# Ollie_DriverMotors.net
KiCad netlist of a schematic drawn in Altium Designer
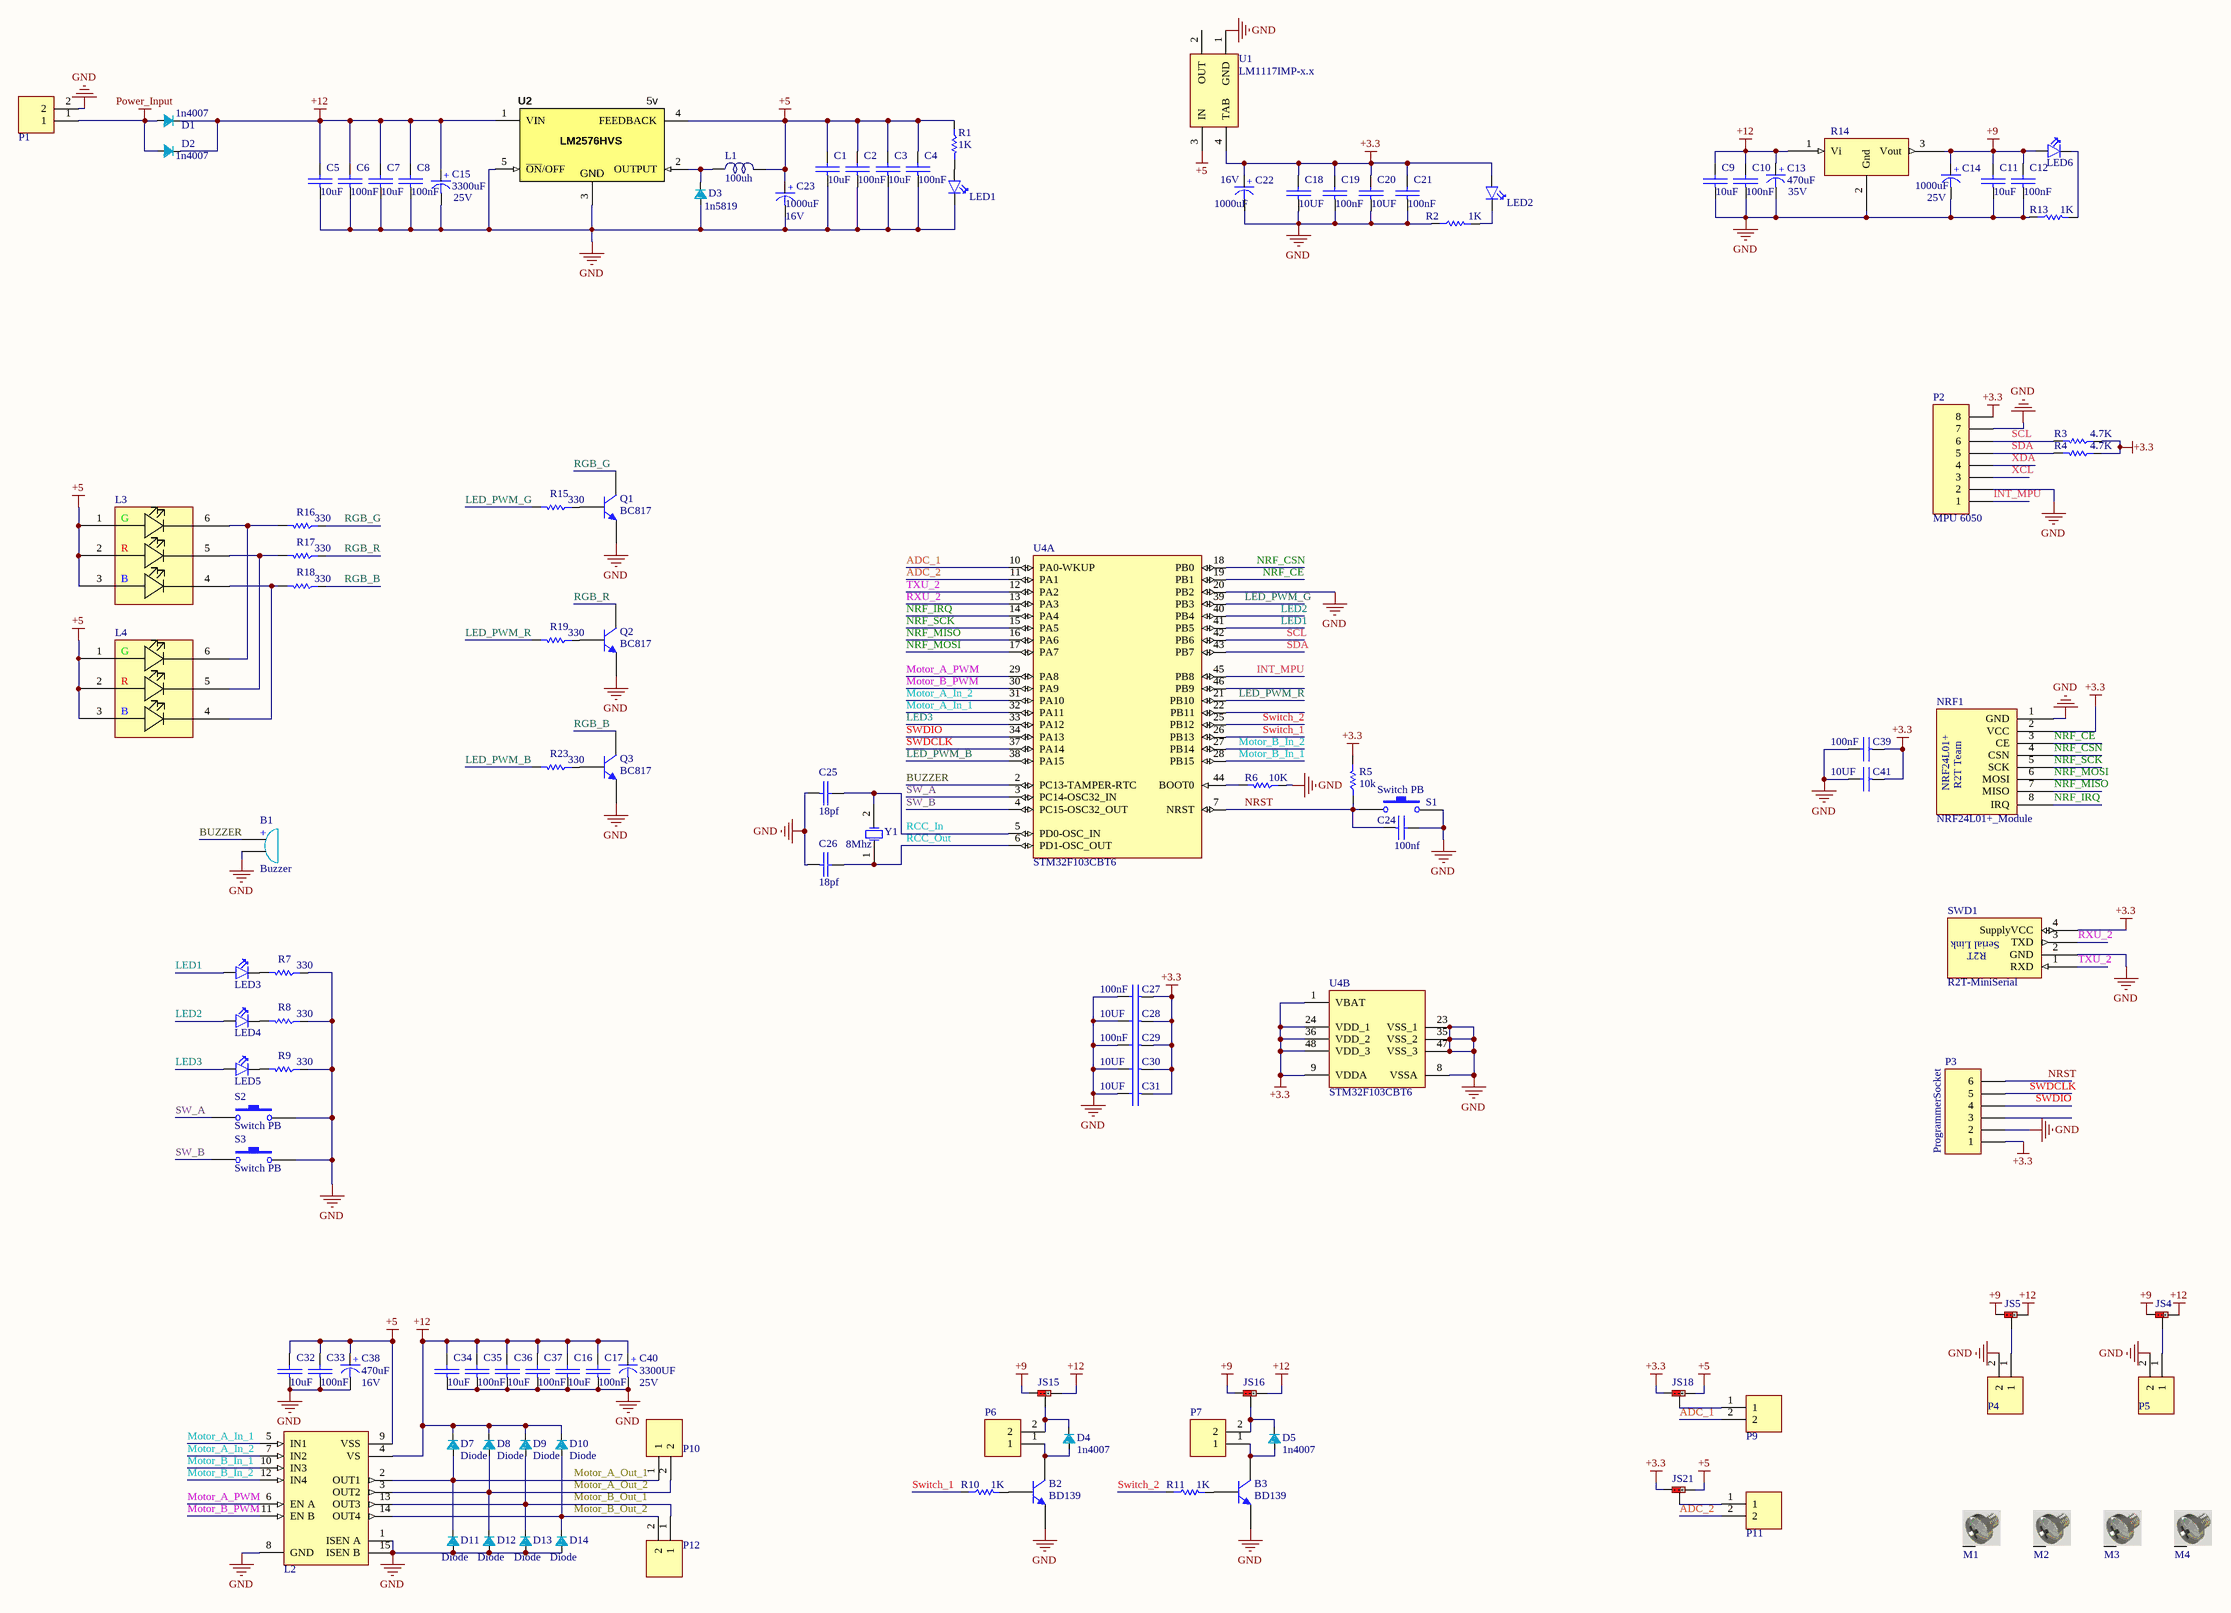
[diagram p0: Ollie_DriverMotors.SchDoc]

(export (version "E")
  (design (tool "Eeschema 10.0.6"))
  (components
    (comp (ref "B1")
      (value "Buzzer")
      (footprint "Buzzer")
      (libsource (lib "R2T Team Library") (part "Buzzer"))
    )
    (comp (ref "B2")
      (value "BD139")
      (footprint "BD139")
      (description "BJT")
      (libsource (lib "My_Lib_BD139") (part "BD139"))
    )
    (comp (ref "B3")
      (value "BD139")
      (footprint "BD139")
      (description "BJT")
      (libsource (lib "My_Lib_BD139") (part "BD139"))
    )
    (comp (ref "C1")
      (value "10uF")
      (footprint "SMD_CAP_1206")
      (description "Bipolar Capacitor")
      (fields (field (name "VOLTAGE") "100V"))
      (libsource (lib "My Library") (part "Cap-Bipolar"))
    )
    (comp (ref "C2")
      (value "100nF")
      (footprint "SMD_CAP_1206")
      (description "Bipolar Capacitor")
      (fields (field (name "VOLTAGE") "100V"))
      (libsource (lib "My Library") (part "Cap-Bipolar"))
    )
    (comp (ref "C3")
      (value "10uF")
      (footprint "SMD_CAP_1206")
      (description "Bipolar Capacitor")
      (fields (field (name "VOLTAGE") "100V"))
      (libsource (lib "My Library") (part "Cap-Bipolar"))
    )
    (comp (ref "C4")
      (value "100nF")
      (footprint "SMD_CAP_1206")
      (description "Bipolar Capacitor")
      (fields (field (name "VOLTAGE") "100V"))
      (libsource (lib "My Library") (part "Cap-Bipolar"))
    )
    (comp (ref "C5")
      (value "10uF")
      (footprint "SMD_CAP_1206")
      (description "Bipolar Capacitor")
      (fields (field (name "VOLTAGE") "100V"))
      (libsource (lib "My Library") (part "Cap-Bipolar"))
    )
    (comp (ref "C6")
      (value "100nF")
      (footprint "SMD_CAP_1206")
      (description "Bipolar Capacitor")
      (fields (field (name "VOLTAGE") "100V"))
      (libsource (lib "My Library") (part "Cap-Bipolar"))
    )
    (comp (ref "C7")
      (value "10uF")
      (footprint "SMD_CAP_1206")
      (description "Bipolar Capacitor")
      (fields (field (name "VOLTAGE") "100V"))
      (libsource (lib "My Library") (part "Cap-Bipolar"))
    )
    (comp (ref "C8")
      (value "100nF")
      (footprint "SMD_CAP_1206")
      (description "Bipolar Capacitor")
      (fields (field (name "VOLTAGE") "100V"))
      (libsource (lib "My Library") (part "Cap-Bipolar"))
    )
    (comp (ref "C9")
      (value "10uF")
      (footprint "SMD_CAP_1206")
      (description "Bipolar Capacitor")
      (fields (field (name "VOLTAGE") "100V"))
      (libsource (lib "My Library") (part "Cap-Bipolar"))
    )
    (comp (ref "C10")
      (value "100nF")
      (footprint "SMD_CAP_1206")
      (description "Bipolar Capacitor")
      (fields (field (name "VOLTAGE") "100V"))
      (libsource (lib "My Library") (part "Cap-Bipolar"))
    )
    (comp (ref "C11")
      (value "10uF")
      (footprint "SMD_CAP_1206")
      (description "Bipolar Capacitor")
      (fields (field (name "VOLTAGE") "100V"))
      (libsource (lib "My Library") (part "Cap-Bipolar"))
    )
    (comp (ref "C12")
      (value "100nF")
      (footprint "SMD_CAP_1206")
      (description "Bipolar Capacitor")
      (fields (field (name "VOLTAGE") "100V"))
      (libsource (lib "My Library") (part "Cap-Bipolar"))
    )
    (comp (ref "C13")
      (value "470uF")
      (footprint "cap 03")
      (description "Polar Capacitor")
      (fields (field (name "VOLTAGE") "35V"))
      (libsource (lib "My Library") (part "Cap-Polar"))
    )
    (comp (ref "C14")
      (value "1000uF")
      (footprint "cap 03")
      (description "Polar Capacitor")
      (fields (field (name "VOLTAGE") "25V"))
      (libsource (lib "My Library") (part "Cap-Polar"))
    )
    (comp (ref "C15")
      (value "3300uF")
      (footprint "CAP 05")
      (description "Polar Capacitor")
      (fields (field (name "VOLTAGE") "25V"))
      (libsource (lib "My Library") (part "Cap-Polar"))
    )
    (comp (ref "C16")
      (value "10uF")
      (footprint "SMD_CAP_1206")
      (description "Bipolar Capacitor")
      (fields (field (name "VOLTAGE") "100V"))
      (libsource (lib "My Library") (part "Cap-Bipolar"))
    )
    (comp (ref "C17")
      (value "100nF")
      (footprint "SMD_CAP_1206")
      (description "Bipolar Capacitor")
      (fields (field (name "VOLTAGE") "100V"))
      (libsource (lib "My Library") (part "Cap-Bipolar"))
    )
    (comp (ref "C18")
      (value "10UF")
      (footprint "SMD_CAP_1206")
      (description "Bipolar Capacitor")
      (fields (field (name "VOLTAGE") "100V"))
      (libsource (lib "My Library") (part "Cap-Bipolar"))
    )
    (comp (ref "C19")
      (value "100nF")
      (footprint "SMD_CAP_1206")
      (description "Bipolar Capacitor")
      (fields (field (name "VOLTAGE") "100V"))
      (libsource (lib "My Library") (part "Cap-Bipolar"))
    )
    (comp (ref "C20")
      (value "10UF")
      (footprint "SMD_CAP_1206")
      (description "Bipolar Capacitor")
      (fields (field (name "VOLTAGE") "100V"))
      (libsource (lib "My Library") (part "Cap-Bipolar"))
    )
    (comp (ref "C21")
      (value "100nF")
      (footprint "SMD_CAP_1206")
      (description "Bipolar Capacitor")
      (fields (field (name "VOLTAGE") "100V"))
      (libsource (lib "My Library") (part "Cap-Bipolar"))
    )
    (comp (ref "C22")
      (value "1000uF")
      (footprint "cap 03")
      (description "Polar Capacitor")
      (fields (field (name "VOLTAGE") "16V"))
      (libsource (lib "My Library") (part "Cap-Polar"))
    )
    (comp (ref "C23")
      (value "1000uF")
      (footprint "cap 04")
      (description "Polar Capacitor")
      (fields (field (name "VOLTAGE") "16V"))
      (libsource (lib "My Library") (part "Cap-Polar"))
    )
    (comp (ref "C24")
      (value "100nf")
      (footprint "SMD_CAP_0805")
      (description "Bipolar Capacitor")
      (fields (field (name "VOLTAGE") "100V"))
      (libsource (lib "My Library") (part "Cap-Bipolar"))
    )
    (comp (ref "C25")
      (value "18pf")
      (footprint "SMD_CAP_0805")
      (description "Bipolar Capacitor")
      (fields (field (name "VOLTAGE") "100V"))
      (libsource (lib "My Library") (part "Cap-Bipolar"))
    )
    (comp (ref "C26")
      (value "18pf")
      (footprint "SMD_CAP_0805")
      (description "Bipolar Capacitor")
      (fields (field (name "VOLTAGE") "100V"))
      (libsource (lib "My Library") (part "Cap-Bipolar"))
    )
    (comp (ref "C27")
      (value "100nF")
      (footprint "SMD_CAP_1206")
      (description "Bipolar Capacitor")
      (fields (field (name "VOLTAGE") "100V"))
      (libsource (lib "My Library") (part "Cap-Bipolar"))
    )
    (comp (ref "C28")
      (value "10UF")
      (footprint "SMD_CAP_1206")
      (description "Bipolar Capacitor")
      (fields (field (name "VOLTAGE") "100V"))
      (libsource (lib "My Library") (part "Cap-Bipolar"))
    )
    (comp (ref "C29")
      (value "100nF")
      (footprint "SMD_CAP_1206")
      (description "Bipolar Capacitor")
      (fields (field (name "VOLTAGE") "100V"))
      (libsource (lib "My Library") (part "Cap-Bipolar"))
    )
    (comp (ref "C30")
      (value "10UF")
      (footprint "SMD_CAP_1206")
      (description "Bipolar Capacitor")
      (fields (field (name "VOLTAGE") "100V"))
      (libsource (lib "My Library") (part "Cap-Bipolar"))
    )
    (comp (ref "C31")
      (value "10UF")
      (footprint "SMD_CAP_1206")
      (description "Bipolar Capacitor")
      (fields (field (name "VOLTAGE") "100V"))
      (libsource (lib "My Library") (part "Cap-Bipolar"))
    )
    (comp (ref "C32")
      (value "10uF")
      (footprint "SMD_CAP_1206")
      (description "Bipolar Capacitor")
      (fields (field (name "VOLTAGE") "100V"))
      (libsource (lib "My Library") (part "Cap-Bipolar"))
    )
    (comp (ref "C33")
      (value "100nF")
      (footprint "SMD_CAP_1206")
      (description "Bipolar Capacitor")
      (fields (field (name "VOLTAGE") "100V"))
      (libsource (lib "My Library") (part "Cap-Bipolar"))
    )
    (comp (ref "C34")
      (value "10uF")
      (footprint "SMD_CAP_1206")
      (description "Bipolar Capacitor")
      (fields (field (name "VOLTAGE") "100V"))
      (libsource (lib "My Library") (part "Cap-Bipolar"))
    )
    (comp (ref "C35")
      (value "100nF")
      (footprint "SMD_CAP_1206")
      (description "Bipolar Capacitor")
      (fields (field (name "VOLTAGE") "100V"))
      (libsource (lib "My Library") (part "Cap-Bipolar"))
    )
    (comp (ref "C36")
      (value "10uF")
      (footprint "SMD_CAP_1206")
      (description "Bipolar Capacitor")
      (fields (field (name "VOLTAGE") "100V"))
      (libsource (lib "My Library") (part "Cap-Bipolar"))
    )
    (comp (ref "C37")
      (value "100nF")
      (footprint "SMD_CAP_1206")
      (description "Bipolar Capacitor")
      (fields (field (name "VOLTAGE") "100V"))
      (libsource (lib "My Library") (part "Cap-Bipolar"))
    )
    (comp (ref "C38")
      (value "470uF")
      (footprint "cap 03")
      (description "Polar Capacitor")
      (fields (field (name "VOLTAGE") "16V"))
      (libsource (lib "My Library") (part "Cap-Polar"))
    )
    (comp (ref "C39")
      (value "100nF")
      (footprint "SMD_CAP_1206")
      (description "Bipolar Capacitor")
      (fields (field (name "VOLTAGE") "100V"))
      (libsource (lib "My Library") (part "Cap-Bipolar"))
    )
    (comp (ref "C40")
      (value "3300UF")
      (footprint "CAP 05")
      (description "Polar Capacitor")
      (fields (field (name "VOLTAGE") "25V"))
      (libsource (lib "My Library") (part "Cap-Polar"))
    )
    (comp (ref "C41")
      (value "10UF")
      (footprint "SMD_CAP_1206")
      (description "Bipolar Capacitor")
      (fields (field (name "VOLTAGE") "100V"))
      (libsource (lib "My Library") (part "Cap-Bipolar"))
    )
    (comp (ref "D1")
      (value "SMD Diodes")
      (footprint "DO-214AC ( SMD Diode )")
      (fields (field (name "DESCRIPTION:") "1n4007"))
      (libsource (lib "R2T Team Library") (part "SMD Diodes"))
    )
    (comp (ref "D2")
      (value "SMD Diodes")
      (footprint "DO-214AC ( SMD Diode )")
      (fields (field (name "DESCRIPTION:") "1n4007"))
      (libsource (lib "R2T Team Library") (part "SMD Diodes"))
    )
    (comp (ref "D3")
      (value "SMD Diodes")
      (footprint "DO-214AC ( SMD Diode )")
      (fields (field (name "DESCRIPTION:") "1n5819"))
      (libsource (lib "R2T Team Library") (part "SMD Diodes"))
    )
    (comp (ref "D4")
      (value "SMD Diodes")
      (footprint "DO-214AC ( SMD Diode )")
      (fields (field (name "DESCRIPTION:") "1n4007"))
      (libsource (lib "R2T Team Library") (part "SMD Diodes"))
    )
    (comp (ref "D5")
      (value "SMD Diodes")
      (footprint "DO-214AC ( SMD Diode )")
      (fields (field (name "DESCRIPTION:") "1n4007"))
      (libsource (lib "R2T Team Library") (part "SMD Diodes"))
    )
    (comp (ref "D7")
      (value "SMD Diodes")
      (footprint "DO-214AC ( SMD Diode )")
      (fields (field (name "DESCRIPTION:") "Diode"))
      (libsource (lib "R2T Team Library") (part "SMD Diodes"))
    )
    (comp (ref "D8")
      (value "SMD Diodes")
      (footprint "DO-214AC ( SMD Diode )")
      (fields (field (name "DESCRIPTION:") "Diode"))
      (libsource (lib "R2T Team Library") (part "SMD Diodes"))
    )
    (comp (ref "D9")
      (value "SMD Diodes")
      (footprint "DO-214AC ( SMD Diode )")
      (fields (field (name "DESCRIPTION:") "Diode"))
      (libsource (lib "R2T Team Library") (part "SMD Diodes"))
    )
    (comp (ref "D10")
      (value "SMD Diodes")
      (footprint "DO-214AC ( SMD Diode )")
      (fields (field (name "DESCRIPTION:") "Diode"))
      (libsource (lib "R2T Team Library") (part "SMD Diodes"))
    )
    (comp (ref "D11")
      (value "SMD Diodes")
      (footprint "DO-214AC ( SMD Diode )")
      (fields (field (name "DESCRIPTION:") "Diode"))
      (libsource (lib "R2T Team Library") (part "SMD Diodes"))
    )
    (comp (ref "D12")
      (value "SMD Diodes")
      (footprint "DO-214AC ( SMD Diode )")
      (fields (field (name "DESCRIPTION:") "Diode"))
      (libsource (lib "R2T Team Library") (part "SMD Diodes"))
    )
    (comp (ref "D13")
      (value "SMD Diodes")
      (footprint "DO-214AC ( SMD Diode )")
      (fields (field (name "DESCRIPTION:") "Diode"))
      (libsource (lib "R2T Team Library") (part "SMD Diodes"))
    )
    (comp (ref "D14")
      (value "SMD Diodes")
      (footprint "DO-214AC ( SMD Diode )")
      (fields (field (name "DESCRIPTION:") "Diode"))
      (libsource (lib "R2T Team Library") (part "SMD Diodes"))
    )
    (comp (ref "JS4")
      (value "JumperSMD 3Pin")
      (footprint "JumperSMD 3Pin")
      (libsource (lib "R2T Team Library") (part "JumperSMD 3Pin"))
    )
    (comp (ref "JS5")
      (value "JumperSMD 3Pin")
      (footprint "JumperSMD 3Pin")
      (libsource (lib "R2T Team Library") (part "JumperSMD 3Pin"))
    )
    (comp (ref "JS15")
      (value "JumperSMD 3Pin")
      (footprint "JumperSMD 3Pin")
      (libsource (lib "R2T Team Library") (part "JumperSMD 3Pin"))
    )
    (comp (ref "JS16")
      (value "JumperSMD 3Pin")
      (footprint "JumperSMD 3Pin")
      (libsource (lib "R2T Team Library") (part "JumperSMD 3Pin"))
    )
    (comp (ref "JS18")
      (value "JumperSMD 3Pin")
      (footprint "JumperSMD 3Pin")
      (libsource (lib "R2T Team Library") (part "JumperSMD 3Pin"))
    )
    (comp (ref "JS21")
      (value "JumperSMD 3Pin")
      (footprint "JumperSMD 3Pin")
      (libsource (lib "R2T Team Library") (part "JumperSMD 3Pin"))
    )
    (comp (ref "L1")
      (value "100uh")
      (footprint "General 10x12(200m) Inductor")
      (libsource (lib "R2T Team Library") (part "Inductor"))
    )
    (comp (ref "L2")
      (value "L298n")
      (footprint "Multiwatt15V")
      (description "Motor Driver")
      (libsource (lib "My_Lib_L298N") (part "L298n"))
    )
    (comp (ref "L3")
      (value "LED RGB")
      (footprint "LED_5050")
      (description "LED 5050 RGB")
      (libsource (lib "My_Lib_LED_RGB_5050") (part "LED RGB"))
    )
    (comp (ref "L4")
      (value "LED RGB")
      (footprint "LED_5050")
      (description "LED 5050 RGB")
      (libsource (lib "My_Lib_LED_RGB_5050") (part "LED RGB"))
    )
    (comp (ref "LED1") (value "LED") (footprint "LED0805") (libsource (lib "R2T Team Library") (part "LED")))
    (comp (ref "LED2") (value "LED") (footprint "LED0805") (libsource (lib "R2T Team Library") (part "LED")))
    (comp (ref "LED3") (value "LED") (footprint "LED0805") (libsource (lib "R2T Team Library") (part "LED")))
    (comp (ref "LED4") (value "LED") (footprint "LED0805") (libsource (lib "R2T Team Library") (part "LED")))
    (comp (ref "LED5") (value "LED") (footprint "LED0805") (libsource (lib "R2T Team Library") (part "LED")))
    (comp (ref "LED6") (value "LED") (footprint "LED0805") (libsource (lib "R2T Team Library") (part "LED")))
    (comp (ref "M1")
      (value "Screw")
      (footprint "Board Screw")
      (description "Board Screw With Spacer")
      (libsource (lib "My Library") (part "Board Screw"))
    )
    (comp (ref "M2")
      (value "Screw")
      (footprint "Board Screw")
      (description "Board Screw With Spacer")
      (libsource (lib "My Library") (part "Board Screw"))
    )
    (comp (ref "M3")
      (value "Screw")
      (footprint "Board Screw")
      (description "Board Screw With Spacer")
      (libsource (lib "My Library") (part "Board Screw"))
    )
    (comp (ref "M4")
      (value "Screw")
      (footprint "Board Screw")
      (description "Board Screw With Spacer")
      (libsource (lib "My Library") (part "Board Screw"))
    )
    (comp (ref "NRF1")
      (value "NRF24L01+_Module")
      (footprint "NRF24L01+_Module-LNA+PA")
      (libsource (lib "R2T Team Library") (part "NRF24L01+_Module"))
    )
    (comp (ref "P1")
      (value "Connector")
      (footprint "Terminal Block 2pin")
      (libsource (lib "") (part "Connector 2Pin_1"))
    )
    (comp (ref "P2")
      (value "MPU 6050")
      (footprint "HDR1X8")
      (description "Header, 8-Pin")
      (libsource (lib "Miscellaneous Connectors") (part "Header 8"))
    )
    (comp (ref "P3")
      (value "ProgrammerSocket")
      (footprint "HDR1X6")
      (description "Header, 6-Pin")
      (libsource (lib "Miscellaneous Connectors") (part "Header 6"))
    )
    (comp (ref "P4")
      (value "Connector")
      (footprint "Polarized Header 2")
      (libsource (lib "") (part "Connector 2Pin_2"))
    )
    (comp (ref "P5")
      (value "Connector")
      (footprint "Polarized Header 2")
      (libsource (lib "") (part "Connector 2Pin_2"))
    )
    (comp (ref "P6")
      (value "Connector")
      (footprint "Polarized Header 2")
      (libsource (lib "") (part "Connector 2Pin_1"))
    )
    (comp (ref "P7")
      (value "Connector")
      (footprint "Polarized Header 2")
      (libsource (lib "") (part "Connector 2Pin_1"))
    )
    (comp (ref "P9")
      (value "Connector")
      (footprint "Polarized Header 2")
      (libsource (lib "") (part "Connector 2Pin_3"))
    )
    (comp (ref "P10")
      (value "Connector")
      (footprint "Terminal Block 2pin")
      (libsource (lib "R2T Team Library") (part "Connector 2Pin"))
    )
    (comp (ref "P11")
      (value "Connector")
      (footprint "Polarized Header 2")
      (libsource (lib "") (part "Connector 2Pin_3"))
    )
    (comp (ref "P12")
      (value "Connector")
      (footprint "Terminal Block 2pin")
      (libsource (lib "") (part "Connector 2Pin_2"))
    )
    (comp (ref "Q1")
      (value "BC817")
      (footprint "SOT23_BEC_N")
      (description "NPN Bipolar Transistor")
      (libsource (lib "My Library") (part "NPN"))
    )
    (comp (ref "Q2")
      (value "BC817")
      (footprint "SOT23_BEC_N")
      (description "NPN Bipolar Transistor")
      (libsource (lib "My Library") (part "NPN"))
    )
    (comp (ref "Q3")
      (value "BC817")
      (footprint "SOT23_BEC_N")
      (description "NPN Bipolar Transistor")
      (libsource (lib "My Library") (part "NPN"))
    )
    (comp (ref "R1")
      (value "1K")
      (footprint "RES 0805 (2012X06L)")
      (description "Resistor")
      (fields (field (name "TOLERANCE") "5%") (field (name "POWER") "1/8 W"))
      (libsource (lib "My Library") (part "Resistor"))
    )
    (comp (ref "R2")
      (value "1K")
      (footprint "RES 0805 (2012X06L)")
      (description "Resistor")
      (fields (field (name "TOLERANCE") "5%") (field (name "POWER") "1/8 W"))
      (libsource (lib "My Library") (part "Resistor"))
    )
    (comp (ref "R3")
      (value "4.7K")
      (footprint "RES 0805 (2012X06L)")
      (description "Resistor")
      (fields (field (name "TOLERANCE") "5%") (field (name "POWER") "1/8 W"))
      (libsource (lib "My Library") (part "Resistor"))
    )
    (comp (ref "R4")
      (value "4.7K")
      (footprint "RES 0805 (2012X06L)")
      (description "Resistor")
      (fields (field (name "TOLERANCE") "5%") (field (name "POWER") "1/8 W"))
      (libsource (lib "My Library") (part "Resistor"))
    )
    (comp (ref "R5")
      (value "10k")
      (footprint "RES 0805 (2012X06L)")
      (description "Resistor")
      (fields (field (name "TOLERANCE") "5%") (field (name "POWER") "1/8 W"))
      (libsource (lib "My Library") (part "Resistor"))
    )
    (comp (ref "R6")
      (value "10K")
      (footprint "RES 0805 (2012X06L)")
      (description "Resistor")
      (fields (field (name "TOLERANCE") "5%") (field (name "POWER") "1/8 W"))
      (libsource (lib "My Library") (part "Resistor"))
    )
    (comp (ref "R7")
      (value "330")
      (footprint "RES 0805 (2012X06L)")
      (description "Resistor")
      (fields (field (name "TOLERANCE") "5%") (field (name "POWER") "1/8 W"))
      (libsource (lib "My Library") (part "Resistor"))
    )
    (comp (ref "R8")
      (value "330")
      (footprint "RES 0805 (2012X06L)")
      (description "Resistor")
      (fields (field (name "TOLERANCE") "5%") (field (name "POWER") "1/8 W"))
      (libsource (lib "My Library") (part "Resistor"))
    )
    (comp (ref "R9")
      (value "330")
      (footprint "RES 0805 (2012X06L)")
      (description "Resistor")
      (fields (field (name "TOLERANCE") "5%") (field (name "POWER") "1/8 W"))
      (libsource (lib "My Library") (part "Resistor"))
    )
    (comp (ref "R10")
      (value "1K")
      (footprint "RES 0805 (2012X06L)")
      (description "Resistor")
      (fields (field (name "TOLERANCE") "5%") (field (name "POWER") "1/8 W"))
      (libsource (lib "My Library") (part "Resistor"))
    )
    (comp (ref "R11")
      (value "1K")
      (footprint "RES 0805 (2012X06L)")
      (description "Resistor")
      (fields (field (name "TOLERANCE") "5%") (field (name "POWER") "1/8 W"))
      (libsource (lib "My Library") (part "Resistor"))
    )
    (comp (ref "R13")
      (value "1K")
      (footprint "RES 0805 (2012X06L)")
      (description "Resistor")
      (fields (field (name "TOLERANCE") "5%") (field (name "POWER") "1/8 W"))
      (libsource (lib "My Library") (part "Resistor"))
    )
    (comp (ref "R14")
      (value "L78XX")
      (footprint "To-220")
      (description "Linear Regulator")
      (libsource (lib "My_Lib_L78XX") (part "L78XX"))
    )
    (comp (ref "R15")
      (value "330")
      (footprint "RES 0805 (2012X06L)")
      (description "Resistor")
      (fields (field (name "TOLERANCE") "5%") (field (name "POWER") "1/8 W"))
      (libsource (lib "My Library") (part "Resistor"))
    )
    (comp (ref "R16")
      (value "330")
      (footprint "RES 0805 (2012X06L)")
      (description "Resistor")
      (fields (field (name "TOLERANCE") "5%") (field (name "POWER") "1/8 W"))
      (libsource (lib "My Library") (part "Resistor"))
    )
    (comp (ref "R17")
      (value "330")
      (footprint "RES 0805 (2012X06L)")
      (description "Resistor")
      (fields (field (name "TOLERANCE") "5%") (field (name "POWER") "1/8 W"))
      (libsource (lib "My Library") (part "Resistor"))
    )
    (comp (ref "R18")
      (value "330")
      (footprint "RES 0805 (2012X06L)")
      (description "Resistor")
      (fields (field (name "TOLERANCE") "5%") (field (name "POWER") "1/8 W"))
      (libsource (lib "My Library") (part "Resistor"))
    )
    (comp (ref "R19")
      (value "330")
      (footprint "RES 0805 (2012X06L)")
      (description "Resistor")
      (fields (field (name "TOLERANCE") "5%") (field (name "POWER") "1/8 W"))
      (libsource (lib "My Library") (part "Resistor"))
    )
    (comp (ref "R23")
      (value "330")
      (footprint "RES 0805 (2012X06L)")
      (description "Resistor")
      (fields (field (name "TOLERANCE") "5%") (field (name "POWER") "1/8 W"))
      (libsource (lib "My Library") (part "Resistor"))
    )
    (comp (ref "S1")
      (value "Switch PB")
      (footprint "SW-PB")
      (description "Push Button Switch")
      (libsource (lib "My Library") (part "Switch PB"))
    )
    (comp (ref "S2")
      (value "Switch PB")
      (footprint "SW-PB")
      (description "Push Button Switch")
      (libsource (lib "My Library") (part "Switch PB"))
    )
    (comp (ref "S3")
      (value "Switch PB")
      (footprint "SW-PB")
      (description "Push Button Switch")
      (libsource (lib "My Library") (part "Switch PB"))
    )
    (comp (ref "SWD1")
      (value "R2T-MiniSerial")
      (footprint "SerialWireMini")
      (libsource (lib "R2T Team Library") (part "R2T-MiniSerial"))
    )
    (comp (ref "U1")
      (value "LM1117IMP-x.x")
      (footprint "MP04A_N")
      (description "x.x Volt, 800mA Low-Dropout Linear Regulator, 4-pin SOT-223")
      (fields
        (field (name "PARTNUMBER") "LM1117IMP-3.3")
        (field (name "MANUFACTURER") "National Semiconductor")
      )
      (libsource (lib "My Library") (part "LM1117IMP-x.x"))
    )
    (comp (ref "U2")
      (value "5v")
      (footprint "TO-263-5")
      (description "Switching Voltage Regulator IC, TO-263-5 SMD, LM2591HVS-5.0")
      (fields
        (field (name "TOLERANCE") "±4%")
        (field (name "MANUFACTURER PART NUMBER 1") "LM2576HVS")
        (field (name "Comment") "Adjustable")
      )
      (libsource (lib "R2T Team Library") (part "LM2576HVS"))
    )
    (comp (ref "U4")
      (value "STM32F103CBT6")
      (footprint "STM-LQFP48_N")
      (libsource (lib "ST Microelectronics STM32 F1") (part "STM32F103CBT6"))
    )
    (comp (ref "Y1")
      (value "8Mhz")
      (footprint "Crystal SMD")
      (description "XTAL Crystal")
      (libsource (lib "My Library") (part "XTAL"))
    )
  )
  (nets
    (net (code "1") (name "+3.3") (class "Default")
      (node (ref "C18") (pin "1") (pinfunction "+_1") (pintype "passive"))
      (node (ref "C19") (pin "1") (pinfunction "+_1") (pintype "passive"))
      (node (ref "C20") (pin "1") (pinfunction "+_1") (pintype "passive"))
      (node (ref "C21") (pin "1") (pinfunction "+_1") (pintype "passive"))
      (node (ref "C22") (pin "1") (pinfunction "+_1") (pintype "passive"))
      (node (ref "C27") (pin "2") (pinfunction "-_2") (pintype "passive"))
      (node (ref "C28") (pin "2") (pinfunction "-_2") (pintype "passive"))
      (node (ref "C29") (pin "2") (pinfunction "-_2") (pintype "passive"))
      (node (ref "C30") (pin "2") (pinfunction "-_2") (pintype "passive"))
      (node (ref "C31") (pin "2") (pinfunction "-_2") (pintype "passive"))
      (node (ref "C39") (pin "2") (pinfunction "-_2") (pintype "passive"))
      (node (ref "C41") (pin "2") (pinfunction "-_2") (pintype "passive"))
      (node (ref "JS18") (pin "3") (pintype "passive"))
      (node (ref "JS21") (pin "3") (pintype "passive"))
      (node (ref "LED2") (pin "1") (pinfunction "A_1") (pintype "passive"))
      (node (ref "NRF1") (pin "2") (pinfunction "VCC_2") (pintype "passive"))
      (node (ref "P2") (pin "8") (pinfunction "8_8") (pintype "passive"))
      (node (ref "P3") (pin "1") (pinfunction "1_1") (pintype "passive"))
      (node (ref "R3") (pin "1") (pinfunction "1_1") (pintype "passive"))
      (node (ref "R4") (pin "1") (pinfunction "1_1") (pintype "passive"))
      (node (ref "R5") (pin "2") (pinfunction "2_2") (pintype "passive"))
      (node (ref "SWD1") (pin "4") (pinfunction "SupplyVCC_4") (pintype "bidirectional"))
      (node (ref "U1") (pin "4") (pinfunction "TAB_4") (pintype "power_in"))
      (node (ref "U4") (pin "1") (pinfunction "VBAT_1") (pintype "power_in"))
      (node (ref "U4") (pin "24") (pinfunction "VDD_1_24") (pintype "power_in"))
      (node (ref "U4") (pin "36") (pinfunction "VDD_2_36") (pintype "power_in"))
      (node (ref "U4") (pin "48") (pinfunction "VDD_3_48") (pintype "power_in"))
      (node (ref "U4") (pin "9") (pinfunction "VDDA_9") (pintype "power_in"))
    )
    (net (code "2") (name "+5") (class "Default")
      (node (ref "C1") (pin "1") (pinfunction "+_1") (pintype "passive"))
      (node (ref "C2") (pin "1") (pinfunction "+_1") (pintype "passive"))
      (node (ref "C23") (pin "1") (pinfunction "+_1") (pintype "passive"))
      (node (ref "C3") (pin "1") (pinfunction "+_1") (pintype "passive"))
      (node (ref "C32") (pin "1") (pinfunction "+_1") (pintype "passive"))
      (node (ref "C33") (pin "1") (pinfunction "+_1") (pintype "passive"))
      (node (ref "C38") (pin "1") (pinfunction "+_1") (pintype "passive"))
      (node (ref "C4") (pin "1") (pinfunction "+_1") (pintype "passive"))
      (node (ref "JS18") (pin "1") (pintype "passive"))
      (node (ref "JS21") (pin "1") (pintype "passive"))
      (node (ref "L1") (pin "2") (pinfunction "2_2") (pintype "passive"))
      (node (ref "L2") (pin "9") (pinfunction "VSS_9") (pintype "power_in"))
      (node (ref "L3") (pin "1") (pinfunction "G_1") (pintype "tri_state"))
      (node (ref "L3") (pin "2") (pinfunction "R_2") (pintype "tri_state"))
      (node (ref "L3") (pin "3") (pinfunction "B_3") (pintype "tri_state"))
      (node (ref "L4") (pin "1") (pinfunction "G_1") (pintype "tri_state"))
      (node (ref "L4") (pin "2") (pinfunction "R_2") (pintype "tri_state"))
      (node (ref "L4") (pin "3") (pinfunction "B_3") (pintype "tri_state"))
      (node (ref "R1") (pin "1") (pinfunction "1_1") (pintype "passive"))
      (node (ref "U1") (pin "3") (pinfunction "IN_3") (pintype "power_in"))
      (node (ref "U2") (pin "4") (pinfunction "FEEDBACK_4") (pintype "power_in"))
    )
    (net (code "3") (name "+9") (class "Default")
      (node (ref "C11") (pin "1") (pinfunction "+_1") (pintype "passive"))
      (node (ref "C12") (pin "1") (pinfunction "+_1") (pintype "passive"))
      (node (ref "C14") (pin "1") (pinfunction "+_1") (pintype "passive"))
      (node (ref "JS15") (pin "3") (pintype "passive"))
      (node (ref "JS16") (pin "3") (pintype "passive"))
      (node (ref "JS4") (pin "3") (pintype "passive"))
      (node (ref "JS5") (pin "3") (pintype "passive"))
      (node (ref "LED6") (pin "1") (pinfunction "A_1") (pintype "passive"))
      (node (ref "R14") (pin "3") (pinfunction "Vout_3") (pintype "output"))
    )
    (net (code "4") (name "+12") (class "Default")
      (node (ref "C10") (pin "1") (pinfunction "+_1") (pintype "passive"))
      (node (ref "C13") (pin "1") (pinfunction "+_1") (pintype "passive"))
      (node (ref "C15") (pin "1") (pinfunction "+_1") (pintype "passive"))
      (node (ref "C16") (pin "1") (pinfunction "+_1") (pintype "passive"))
      (node (ref "C17") (pin "1") (pinfunction "+_1") (pintype "passive"))
      (node (ref "C34") (pin "1") (pinfunction "+_1") (pintype "passive"))
      (node (ref "C35") (pin "1") (pinfunction "+_1") (pintype "passive"))
      (node (ref "C36") (pin "1") (pinfunction "+_1") (pintype "passive"))
      (node (ref "C37") (pin "1") (pinfunction "+_1") (pintype "passive"))
      (node (ref "C40") (pin "1") (pinfunction "+_1") (pintype "passive"))
      (node (ref "C5") (pin "1") (pinfunction "+_1") (pintype "passive"))
      (node (ref "C6") (pin "1") (pinfunction "+_1") (pintype "passive"))
      (node (ref "C7") (pin "1") (pinfunction "+_1") (pintype "passive"))
      (node (ref "C8") (pin "1") (pinfunction "+_1") (pintype "passive"))
      (node (ref "C9") (pin "1") (pinfunction "+_1") (pintype "passive"))
      (node (ref "D1") (pin "1") (pintype "passive"))
      (node (ref "D10") (pin "1") (pintype "passive"))
      (node (ref "D2") (pin "1") (pintype "passive"))
      (node (ref "D7") (pin "1") (pintype "passive"))
      (node (ref "D8") (pin "1") (pintype "passive"))
      (node (ref "D9") (pin "1") (pintype "passive"))
      (node (ref "JS15") (pin "1") (pintype "passive"))
      (node (ref "JS16") (pin "1") (pintype "passive"))
      (node (ref "JS4") (pin "1") (pintype "passive"))
      (node (ref "JS5") (pin "1") (pintype "passive"))
      (node (ref "L2") (pin "4") (pinfunction "VS_4") (pintype "power_in"))
      (node (ref "R14") (pin "1") (pinfunction "Vi_1") (pintype "input"))
      (node (ref "U2") (pin "1") (pinfunction "VIN_1") (pintype "power_in"))
    )
    (net (code "5") (name "/ADC_1") (class "Default")
      (node (ref "P9") (pin "2") (pinfunction "2_2") (pintype "passive"))
      (node (ref "U4") (pin "10") (pinfunction "PA0-WKUP_10") (pintype "bidirectional"))
    )
    (net (code "6") (name "/ADC_2") (class "Default")
      (node (ref "P11") (pin "2") (pinfunction "2_2") (pintype "passive"))
      (node (ref "U4") (pin "11") (pinfunction "PA1_11") (pintype "bidirectional"))
    )
    (net (code "7") (name "/BUZZER") (class "Default")
      (node (ref "B1") (pin "1") (pinfunction "VCC_1") (pintype "passive"))
      (node (ref "U4") (pin "2") (pinfunction "PC13-TAMPER-RTC_2") (pintype "bidirectional"))
    )
    (net (code "8") (name "/INT_MPU") (class "Default")
      (node (ref "P2") (pin "1") (pinfunction "1_1") (pintype "passive"))
      (node (ref "U4") (pin "45") (pinfunction "PB8_45") (pintype "bidirectional"))
    )
    (net (code "9") (name "/LED1") (class "Default")
      (node (ref "LED3") (pin "1") (pinfunction "A_1") (pintype "passive"))
      (node (ref "U4") (pin "41") (pinfunction "PB5_41") (pintype "bidirectional"))
    )
    (net (code "10") (name "/LED2") (class "Default")
      (node (ref "LED4") (pin "1") (pinfunction "A_1") (pintype "passive"))
      (node (ref "U4") (pin "40") (pinfunction "PB4_40") (pintype "bidirectional"))
    )
    (net (code "11") (name "/LED3") (class "Default")
      (node (ref "LED5") (pin "1") (pinfunction "A_1") (pintype "passive"))
      (node (ref "U4") (pin "33") (pinfunction "PA12_33") (pintype "bidirectional"))
    )
    (net (code "12") (name "/LED_PWM_B") (class "Default")
      (node (ref "R23") (pin "2") (pinfunction "2_2") (pintype "passive"))
      (node (ref "U4") (pin "38") (pinfunction "PA15_38") (pintype "bidirectional"))
    )
    (net (code "13") (name "/LED_PWM_G") (class "Default")
      (node (ref "R15") (pin "2") (pinfunction "2_2") (pintype "passive"))
      (node (ref "U4") (pin "39") (pinfunction "PB3_39") (pintype "bidirectional"))
    )
    (net (code "14") (name "/LED_PWM_R") (class "Default")
      (node (ref "R19") (pin "2") (pinfunction "2_2") (pintype "passive"))
      (node (ref "U4") (pin "21") (pinfunction "PB10_21") (pintype "bidirectional"))
    )
    (net (code "15") (name "/Motor_A_In_1") (class "Default")
      (node (ref "L2") (pin "5") (pinfunction "IN1_5") (pintype "input"))
      (node (ref "U4") (pin "32") (pinfunction "PA11_32") (pintype "bidirectional"))
    )
    (net (code "16") (name "/Motor_A_In_2") (class "Default")
      (node (ref "L2") (pin "7") (pinfunction "IN2_7") (pintype "input"))
      (node (ref "U4") (pin "31") (pinfunction "PA10_31") (pintype "bidirectional"))
    )
    (net (code "17") (name "/Motor_A_Out_1") (class "Default")
      (node (ref "D11") (pin "1") (pintype "passive"))
      (node (ref "D7") (pin "0") (pintype "passive"))
      (node (ref "L2") (pin "2") (pinfunction "OUT1_2") (pintype "output"))
      (node (ref "P10") (pin "1") (pinfunction "1_1") (pintype "passive"))
    )
    (net (code "18") (name "/Motor_A_Out_2") (class "Default")
      (node (ref "D12") (pin "1") (pintype "passive"))
      (node (ref "D8") (pin "0") (pintype "passive"))
      (node (ref "L2") (pin "3") (pinfunction "OUT2_3") (pintype "output"))
      (node (ref "P10") (pin "2") (pinfunction "2_2") (pintype "passive"))
    )
    (net (code "19") (name "/Motor_A_PWM") (class "Default")
      (node (ref "L2") (pin "6") (pinfunction "EN_A_6") (pintype "input"))
      (node (ref "U4") (pin "29") (pinfunction "PA8_29") (pintype "bidirectional"))
    )
    (net (code "20") (name "/Motor_B_In_1") (class "Default")
      (node (ref "L2") (pin "10") (pinfunction "IN3_10") (pintype "input"))
      (node (ref "U4") (pin "28") (pinfunction "PB15_28") (pintype "bidirectional"))
    )
    (net (code "21") (name "/Motor_B_In_2") (class "Default")
      (node (ref "L2") (pin "12") (pinfunction "IN4_12") (pintype "input"))
      (node (ref "U4") (pin "27") (pinfunction "PB14_27") (pintype "bidirectional"))
    )
    (net (code "22") (name "/Motor_B_Out_1") (class "Default")
      (node (ref "D13") (pin "1") (pintype "passive"))
      (node (ref "D9") (pin "0") (pintype "passive"))
      (node (ref "L2") (pin "13") (pinfunction "OUT3_13") (pintype "output"))
      (node (ref "P12") (pin "1") (pinfunction "1_1") (pintype "passive"))
    )
    (net (code "23") (name "/Motor_B_Out_2") (class "Default")
      (node (ref "D10") (pin "0") (pintype "passive"))
      (node (ref "D14") (pin "1") (pintype "passive"))
      (node (ref "L2") (pin "14") (pinfunction "OUT4_14") (pintype "output"))
      (node (ref "P12") (pin "2") (pinfunction "2_2") (pintype "passive"))
    )
    (net (code "24") (name "/Motor_B_PWM") (class "Default")
      (node (ref "L2") (pin "11") (pinfunction "EN_B_11") (pintype "input"))
      (node (ref "U4") (pin "30") (pinfunction "PA9_30") (pintype "bidirectional"))
    )
    (net (code "25") (name "/NRF_CE") (class "Default")
      (node (ref "NRF1") (pin "3") (pinfunction "CE_3") (pintype "passive"))
      (node (ref "U4") (pin "19") (pinfunction "PB1_19") (pintype "bidirectional"))
    )
    (net (code "26") (name "/NRF_CSN") (class "Default")
      (node (ref "NRF1") (pin "4") (pinfunction "CSN_4") (pintype "passive"))
      (node (ref "U4") (pin "18") (pinfunction "PB0_18") (pintype "bidirectional"))
    )
    (net (code "27") (name "/NRF_IRQ") (class "Default")
      (node (ref "NRF1") (pin "8") (pinfunction "IRQ_8") (pintype "passive"))
      (node (ref "U4") (pin "14") (pinfunction "PA4_14") (pintype "bidirectional"))
    )
    (net (code "28") (name "/NRF_MISO") (class "Default")
      (node (ref "NRF1") (pin "7") (pinfunction "MISO_7") (pintype "passive"))
      (node (ref "U4") (pin "16") (pinfunction "PA6_16") (pintype "bidirectional"))
    )
    (net (code "29") (name "/NRF_MOSI") (class "Default")
      (node (ref "NRF1") (pin "6") (pinfunction "MOSI_6") (pintype "passive"))
      (node (ref "U4") (pin "17") (pinfunction "PA7_17") (pintype "bidirectional"))
    )
    (net (code "30") (name "/NRF_SCK") (class "Default")
      (node (ref "NRF1") (pin "5") (pinfunction "SCK_5") (pintype "passive"))
      (node (ref "U4") (pin "15") (pinfunction "PA5_15") (pintype "bidirectional"))
    )
    (net (code "31") (name "/NRST") (class "Default")
      (node (ref "C24") (pin "2") (pinfunction "-_2") (pintype "passive"))
      (node (ref "P3") (pin "6") (pinfunction "6_6") (pintype "passive"))
      (node (ref "R5") (pin "1") (pinfunction "1_1") (pintype "passive"))
      (node (ref "S1") (pin "1") (pinfunction "1_1") (pintype "passive"))
      (node (ref "U4") (pin "7") (pinfunction "NRST_7") (pintype "bidirectional"))
    )
    (net (code "32") (name "/RCC_In") (class "Default")
      (node (ref "C25") (pin "1") (pinfunction "+_1") (pintype "passive"))
      (node (ref "U4") (pin "5") (pinfunction "PD0-OSC_IN_5") (pintype "bidirectional"))
      (node (ref "Y1") (pin "2") (pinfunction "OSC2_2") (pintype "passive"))
    )
    (net (code "33") (name "/RCC_Out") (class "Default")
      (node (ref "C26") (pin "1") (pinfunction "+_1") (pintype "passive"))
      (node (ref "U4") (pin "6") (pinfunction "PD1-OSC_OUT_6") (pintype "bidirectional"))
      (node (ref "Y1") (pin "1") (pinfunction "OSC1_1") (pintype "passive"))
    )
    (net (code "34") (name "/RGB_B") (class "Default")
      (node (ref "Q3") (pin "3") (pinfunction "C_3") (pintype "passive"))
      (node (ref "R18") (pin "1") (pinfunction "1_1") (pintype "passive"))
    )
    (net (code "35") (name "/RGB_G") (class "Default")
      (node (ref "Q1") (pin "3") (pinfunction "C_3") (pintype "passive"))
      (node (ref "R16") (pin "1") (pinfunction "1_1") (pintype "passive"))
    )
    (net (code "36") (name "/RGB_R") (class "Default")
      (node (ref "Q2") (pin "3") (pinfunction "C_3") (pintype "passive"))
      (node (ref "R17") (pin "1") (pinfunction "1_1") (pintype "passive"))
    )
    (net (code "37") (name "/RXU_2") (class "Default")
      (node (ref "SWD1") (pin "3") (pinfunction "TXD_3") (pintype "output"))
      (node (ref "U4") (pin "13") (pinfunction "PA3_13") (pintype "bidirectional"))
    )
    (net (code "38") (name "/SCL") (class "Default")
      (node (ref "P2") (pin "6") (pinfunction "6_6") (pintype "passive"))
      (node (ref "R3") (pin "2") (pinfunction "2_2") (pintype "passive"))
      (node (ref "U4") (pin "42") (pinfunction "PB6_42") (pintype "bidirectional"))
    )
    (net (code "39") (name "/SDA") (class "Default")
      (node (ref "P2") (pin "5") (pinfunction "5_5") (pintype "passive"))
      (node (ref "R4") (pin "2") (pinfunction "2_2") (pintype "passive"))
      (node (ref "U4") (pin "43") (pinfunction "PB7_43") (pintype "bidirectional"))
    )
    (net (code "40") (name "/SWDCLK") (class "Default")
      (node (ref "P3") (pin "5") (pinfunction "5_5") (pintype "passive"))
      (node (ref "U4") (pin "37") (pinfunction "PA14_37") (pintype "bidirectional"))
    )
    (net (code "41") (name "/SWDIO") (class "Default")
      (node (ref "P3") (pin "4") (pinfunction "4_4") (pintype "passive"))
      (node (ref "U4") (pin "34") (pinfunction "PA13_34") (pintype "bidirectional"))
    )
    (net (code "42") (name "/SW_A") (class "Default")
      (node (ref "S2") (pin "1") (pinfunction "1_1") (pintype "passive"))
      (node (ref "U4") (pin "3") (pinfunction "PC14-OSC32_IN_3") (pintype "bidirectional"))
    )
    (net (code "43") (name "/SW_B") (class "Default")
      (node (ref "S3") (pin "1") (pinfunction "1_1") (pintype "passive"))
      (node (ref "U4") (pin "4") (pinfunction "PC15-OSC32_OUT_4") (pintype "bidirectional"))
    )
    (net (code "44") (name "/Switch_1") (class "Default")
      (node (ref "R10") (pin "1") (pinfunction "1_1") (pintype "passive"))
      (node (ref "U4") (pin "26") (pinfunction "PB13_26") (pintype "bidirectional"))
    )
    (net (code "45") (name "/Switch_2") (class "Default")
      (node (ref "R11") (pin "1") (pinfunction "1_1") (pintype "passive"))
      (node (ref "U4") (pin "25") (pinfunction "PB12_25") (pintype "bidirectional"))
    )
    (net (code "46") (name "/TXU_2") (class "Default")
      (node (ref "SWD1") (pin "1") (pinfunction "RXD_1") (pintype "input"))
      (node (ref "U4") (pin "12") (pinfunction "PA2_12") (pintype "bidirectional"))
    )
    (net (code "47") (name "/XCL") (class "Default")
      (node (ref "P2") (pin "3") (pinfunction "3_3") (pintype "passive"))
    )
    (net (code "48") (name "/XDA") (class "Default")
      (node (ref "P2") (pin "4") (pinfunction "4_4") (pintype "passive"))
    )
    (net (code "49") (name "GND") (class "Default")
      (node (ref "B1") (pin "2") (pinfunction "GND_2") (pintype "passive"))
      (node (ref "B2") (pin "E") (pinfunction "E_E") (pintype "passive"))
      (node (ref "B3") (pin "E") (pinfunction "E_E") (pintype "passive"))
      (node (ref "C1") (pin "2") (pinfunction "-_2") (pintype "passive"))
      (node (ref "C10") (pin "2") (pinfunction "-_2") (pintype "passive"))
      (node (ref "C11") (pin "2") (pinfunction "-_2") (pintype "passive"))
      (node (ref "C12") (pin "2") (pinfunction "-_2") (pintype "passive"))
      (node (ref "C13") (pin "2") (pinfunction "-_2") (pintype "passive"))
      (node (ref "C14") (pin "2") (pinfunction "-_2") (pintype "passive"))
      (node (ref "C15") (pin "2") (pinfunction "-_2") (pintype "passive"))
      (node (ref "C16") (pin "2") (pinfunction "-_2") (pintype "passive"))
      (node (ref "C17") (pin "2") (pinfunction "-_2") (pintype "passive"))
      (node (ref "C18") (pin "2") (pinfunction "-_2") (pintype "passive"))
      (node (ref "C19") (pin "2") (pinfunction "-_2") (pintype "passive"))
      (node (ref "C2") (pin "2") (pinfunction "-_2") (pintype "passive"))
      (node (ref "C20") (pin "2") (pinfunction "-_2") (pintype "passive"))
      (node (ref "C21") (pin "2") (pinfunction "-_2") (pintype "passive"))
      (node (ref "C22") (pin "2") (pinfunction "-_2") (pintype "passive"))
      (node (ref "C23") (pin "2") (pinfunction "-_2") (pintype "passive"))
      (node (ref "C24") (pin "1") (pinfunction "+_1") (pintype "passive"))
      (node (ref "C25") (pin "2") (pinfunction "-_2") (pintype "passive"))
      (node (ref "C26") (pin "2") (pinfunction "-_2") (pintype "passive"))
      (node (ref "C27") (pin "1") (pinfunction "+_1") (pintype "passive"))
      (node (ref "C28") (pin "1") (pinfunction "+_1") (pintype "passive"))
      (node (ref "C29") (pin "1") (pinfunction "+_1") (pintype "passive"))
      (node (ref "C3") (pin "2") (pinfunction "-_2") (pintype "passive"))
      (node (ref "C30") (pin "1") (pinfunction "+_1") (pintype "passive"))
      (node (ref "C31") (pin "1") (pinfunction "+_1") (pintype "passive"))
      (node (ref "C32") (pin "2") (pinfunction "-_2") (pintype "passive"))
      (node (ref "C33") (pin "2") (pinfunction "-_2") (pintype "passive"))
      (node (ref "C34") (pin "2") (pinfunction "-_2") (pintype "passive"))
      (node (ref "C35") (pin "2") (pinfunction "-_2") (pintype "passive"))
      (node (ref "C36") (pin "2") (pinfunction "-_2") (pintype "passive"))
      (node (ref "C37") (pin "2") (pinfunction "-_2") (pintype "passive"))
      (node (ref "C38") (pin "2") (pinfunction "-_2") (pintype "passive"))
      (node (ref "C39") (pin "1") (pinfunction "+_1") (pintype "passive"))
      (node (ref "C4") (pin "2") (pinfunction "-_2") (pintype "passive"))
      (node (ref "C40") (pin "2") (pinfunction "-_2") (pintype "passive"))
      (node (ref "C41") (pin "1") (pinfunction "+_1") (pintype "passive"))
      (node (ref "C5") (pin "2") (pinfunction "-_2") (pintype "passive"))
      (node (ref "C6") (pin "2") (pinfunction "-_2") (pintype "passive"))
      (node (ref "C7") (pin "2") (pinfunction "-_2") (pintype "passive"))
      (node (ref "C8") (pin "2") (pinfunction "-_2") (pintype "passive"))
      (node (ref "C9") (pin "2") (pinfunction "-_2") (pintype "passive"))
      (node (ref "D11") (pin "0") (pintype "passive"))
      (node (ref "D12") (pin "0") (pintype "passive"))
      (node (ref "D13") (pin "0") (pintype "passive"))
      (node (ref "D14") (pin "0") (pintype "passive"))
      (node (ref "D3") (pin "0") (pintype "passive"))
      (node (ref "L2") (pin "1") (pinfunction "ISEN_A_1") (pintype "passive"))
      (node (ref "L2") (pin "15") (pinfunction "ISEN_B_15") (pintype "passive"))
      (node (ref "L2") (pin "8") (pinfunction "GND_8") (pintype "power_in"))
      (node (ref "LED1") (pin "2") (pinfunction "K_2") (pintype "passive"))
      (node (ref "NRF1") (pin "1") (pinfunction "GND_1") (pintype "passive"))
      (node (ref "P1") (pin "2") (pinfunction "2_2") (pintype "passive"))
      (node (ref "P2") (pin "2") (pinfunction "2_2") (pintype "passive"))
      (node (ref "P2") (pin "7") (pinfunction "7_7") (pintype "passive"))
      (node (ref "P3") (pin "2") (pinfunction "2_2") (pintype "passive"))
      (node (ref "P4") (pin "2") (pinfunction "2_2") (pintype "passive"))
      (node (ref "P5") (pin "2") (pinfunction "2_2") (pintype "passive"))
      (node (ref "Q1") (pin "2") (pinfunction "E_2") (pintype "passive"))
      (node (ref "Q2") (pin "2") (pinfunction "E_2") (pintype "passive"))
      (node (ref "Q3") (pin "2") (pinfunction "E_2") (pintype "passive"))
      (node (ref "R13") (pin "1") (pinfunction "1_1") (pintype "passive"))
      (node (ref "R14") (pin "2") (pinfunction "Gnd_2") (pintype "passive"))
      (node (ref "R2") (pin "1") (pinfunction "1_1") (pintype "passive"))
      (node (ref "R6") (pin "1") (pinfunction "1_1") (pintype "passive"))
      (node (ref "R7") (pin "1") (pinfunction "1_1") (pintype "passive"))
      (node (ref "R8") (pin "1") (pinfunction "1_1") (pintype "passive"))
      (node (ref "R9") (pin "1") (pinfunction "1_1") (pintype "passive"))
      (node (ref "S1") (pin "2") (pinfunction "2_2") (pintype "passive"))
      (node (ref "S2") (pin "2") (pinfunction "2_2") (pintype "passive"))
      (node (ref "S3") (pin "2") (pinfunction "2_2") (pintype "passive"))
      (node (ref "SWD1") (pin "2") (pinfunction "GND_2") (pintype "passive"))
      (node (ref "U1") (pin "1") (pinfunction "GND_1") (pintype "power_in"))
      (node (ref "U2") (pin "3") (pinfunction "GND_3") (pintype "power_in"))
      (node (ref "U2") (pin "5") (pinfunction "~{ON}/OFF_5") (pintype "input"))
      (node (ref "U4") (pin "20") (pinfunction "PB2_20") (pintype "bidirectional"))
      (node (ref "U4") (pin "23") (pinfunction "VSS_1_23") (pintype "power_in"))
      (node (ref "U4") (pin "35") (pinfunction "VSS_2_35") (pintype "power_in"))
      (node (ref "U4") (pin "47") (pinfunction "VSS_3_47") (pintype "power_in"))
      (node (ref "U4") (pin "8") (pinfunction "VSSA_8") (pintype "power_in"))
    )
    (net (code "50") (name "Net-(B2-PadB)") (class "Default")
      (node (ref "B2") (pin "B") (pinfunction "B_B") (pintype "passive"))
      (node (ref "R10") (pin "2") (pinfunction "2_2") (pintype "passive"))
    )
    (net (code "51") (name "Net-(B2-PadC)") (class "Default")
      (node (ref "B2") (pin "C") (pinfunction "C_C") (pintype "passive"))
      (node (ref "D4") (pin "0") (pintype "passive"))
      (node (ref "P6") (pin "1") (pinfunction "1_1") (pintype "passive"))
    )
    (net (code "52") (name "Net-(B3-PadB)") (class "Default")
      (node (ref "B3") (pin "B") (pinfunction "B_B") (pintype "passive"))
      (node (ref "R11") (pin "2") (pinfunction "2_2") (pintype "passive"))
    )
    (net (code "53") (name "Net-(B3-PadC)") (class "Default")
      (node (ref "B3") (pin "C") (pinfunction "C_C") (pintype "passive"))
      (node (ref "D5") (pin "0") (pintype "passive"))
      (node (ref "P7") (pin "1") (pinfunction "1_1") (pintype "passive"))
    )
    (net (code "54") (name "Net-(D4-Pad1)") (class "Default")
      (node (ref "D4") (pin "1") (pintype "passive"))
      (node (ref "JS15") (pin "2") (pintype "passive"))
      (node (ref "P6") (pin "2") (pinfunction "2_2") (pintype "passive"))
    )
    (net (code "55") (name "Net-(D5-Pad1)") (class "Default")
      (node (ref "D5") (pin "1") (pintype "passive"))
      (node (ref "JS16") (pin "2") (pintype "passive"))
      (node (ref "P7") (pin "2") (pinfunction "2_2") (pintype "passive"))
    )
    (net (code "56") (name "Net-(JS4-Pad2)") (class "Default")
      (node (ref "JS4") (pin "2") (pintype "passive"))
      (node (ref "P5") (pin "1") (pinfunction "1_1") (pintype "passive"))
    )
    (net (code "57") (name "Net-(JS5-Pad2)") (class "Default")
      (node (ref "JS5") (pin "2") (pintype "passive"))
      (node (ref "P4") (pin "1") (pinfunction "1_1") (pintype "passive"))
    )
    (net (code "58") (name "Net-(JS18-Pad2)") (class "Default")
      (node (ref "JS18") (pin "2") (pintype "passive"))
      (node (ref "P9") (pin "1") (pinfunction "1_1") (pintype "passive"))
    )
    (net (code "59") (name "Net-(JS21-Pad2)") (class "Default")
      (node (ref "JS21") (pin "2") (pintype "passive"))
      (node (ref "P11") (pin "1") (pinfunction "1_1") (pintype "passive"))
    )
    (net (code "60") (name "Net-(L3-Pad4)") (class "Default")
      (node (ref "L3") (pin "4") (pinfunction "4_4") (pintype "tri_state"))
      (node (ref "L4") (pin "4") (pinfunction "4_4") (pintype "tri_state"))
      (node (ref "R18") (pin "2") (pinfunction "2_2") (pintype "passive"))
    )
    (net (code "61") (name "Net-(L3-Pad5)") (class "Default")
      (node (ref "L3") (pin "5") (pinfunction "5_5") (pintype "tri_state"))
      (node (ref "L4") (pin "5") (pinfunction "5_5") (pintype "tri_state"))
      (node (ref "R17") (pin "2") (pinfunction "2_2") (pintype "passive"))
    )
    (net (code "62") (name "Net-(L3-Pad6)") (class "Default")
      (node (ref "L3") (pin "6") (pinfunction "6_6") (pintype "tri_state"))
      (node (ref "L4") (pin "6") (pinfunction "6_6") (pintype "tri_state"))
      (node (ref "R16") (pin "2") (pinfunction "2_2") (pintype "passive"))
    )
    (net (code "63") (name "Net-(LED1-A)") (class "Default")
      (node (ref "LED1") (pin "1") (pinfunction "A_1") (pintype "passive"))
      (node (ref "R1") (pin "2") (pinfunction "2_2") (pintype "passive"))
    )
    (net (code "64") (name "Net-(LED2-K)") (class "Default")
      (node (ref "LED2") (pin "2") (pinfunction "K_2") (pintype "passive"))
      (node (ref "R2") (pin "2") (pinfunction "2_2") (pintype "passive"))
    )
    (net (code "65") (name "Net-(LED3-K)") (class "Default")
      (node (ref "LED3") (pin "2") (pinfunction "K_2") (pintype "passive"))
      (node (ref "R7") (pin "2") (pinfunction "2_2") (pintype "passive"))
    )
    (net (code "66") (name "Net-(LED4-K)") (class "Default")
      (node (ref "LED4") (pin "2") (pinfunction "K_2") (pintype "passive"))
      (node (ref "R8") (pin "2") (pinfunction "2_2") (pintype "passive"))
    )
    (net (code "67") (name "Net-(LED5-K)") (class "Default")
      (node (ref "LED5") (pin "2") (pinfunction "K_2") (pintype "passive"))
      (node (ref "R9") (pin "2") (pinfunction "2_2") (pintype "passive"))
    )
    (net (code "68") (name "Net-(LED6-K)") (class "Default")
      (node (ref "LED6") (pin "2") (pinfunction "K_2") (pintype "passive"))
      (node (ref "R13") (pin "2") (pinfunction "2_2") (pintype "passive"))
    )
    (net (code "69") (name "Net-(Q1-B)") (class "Default")
      (node (ref "Q1") (pin "1") (pinfunction "B_1") (pintype "passive"))
      (node (ref "R15") (pin "1") (pinfunction "1_1") (pintype "passive"))
    )
    (net (code "70") (name "Net-(Q2-B)") (class "Default")
      (node (ref "Q2") (pin "1") (pinfunction "B_1") (pintype "passive"))
      (node (ref "R19") (pin "1") (pinfunction "1_1") (pintype "passive"))
    )
    (net (code "71") (name "Net-(Q3-B)") (class "Default")
      (node (ref "Q3") (pin "1") (pinfunction "B_1") (pintype "passive"))
      (node (ref "R23") (pin "1") (pinfunction "1_1") (pintype "passive"))
    )
    (net (code "72") (name "Net-(U2-OUTPUT)") (class "Default")
      (node (ref "D3") (pin "1") (pintype "passive"))
      (node (ref "L1") (pin "1") (pinfunction "1_1") (pintype "passive"))
      (node (ref "U2") (pin "2") (pinfunction "OUTPUT_2") (pintype "input"))
    )
    (net (code "73") (name "Net-(U4A-BOOT0)") (class "Default")
      (node (ref "R6") (pin "2") (pinfunction "2_2") (pintype "passive"))
      (node (ref "U4") (pin "44") (pinfunction "BOOT0_44") (pintype "input"))
    )
    (net (code "74") (name "Power_Input") (class "Default")
      (node (ref "D1") (pin "0") (pintype "passive"))
      (node (ref "D2") (pin "0") (pintype "passive"))
      (node (ref "P1") (pin "1") (pinfunction "1_1") (pintype "passive"))
    )
    (net (code "75") (name "unconnected-(M1-PadS)") (class "Default")
      (node (ref "M1") (pin "S") (pinfunction "S_S") (pintype "passive"))
    )
    (net (code "76") (name "unconnected-(M2-PadS)") (class "Default")
      (node (ref "M2") (pin "S") (pinfunction "S_S") (pintype "passive"))
    )
    (net (code "77") (name "unconnected-(M3-PadS)") (class "Default")
      (node (ref "M3") (pin "S") (pinfunction "S_S") (pintype "passive"))
    )
    (net (code "78") (name "unconnected-(M4-PadS)") (class "Default")
      (node (ref "M4") (pin "S") (pinfunction "S_S") (pintype "passive"))
    )
    (net (code "79") (name "unconnected-(P3-Pad3)") (class "Default")
      (node (ref "P3") (pin "3") (pinfunction "3_3") (pintype "passive"))
    )
    (net (code "80") (name "unconnected-(U1-OUT-Pad2)") (class "Default")
      (node (ref "U1") (pin "2") (pinfunction "OUT_2") (pintype "power_in"))
    )
    (net (code "81") (name "unconnected-(U4A-PB9-Pad46)") (class "Default")
      (node (ref "U4") (pin "46") (pinfunction "PB9_46") (pintype "bidirectional"))
    )
    (net (code "82") (name "unconnected-(U4A-PB11-Pad22)") (class "Default")
      (node (ref "U4") (pin "22") (pinfunction "PB11_22") (pintype "bidirectional"))
    )
  )
)
